# pic_circuit.net
KiCad netlist of a schematic drawn in EAGLE
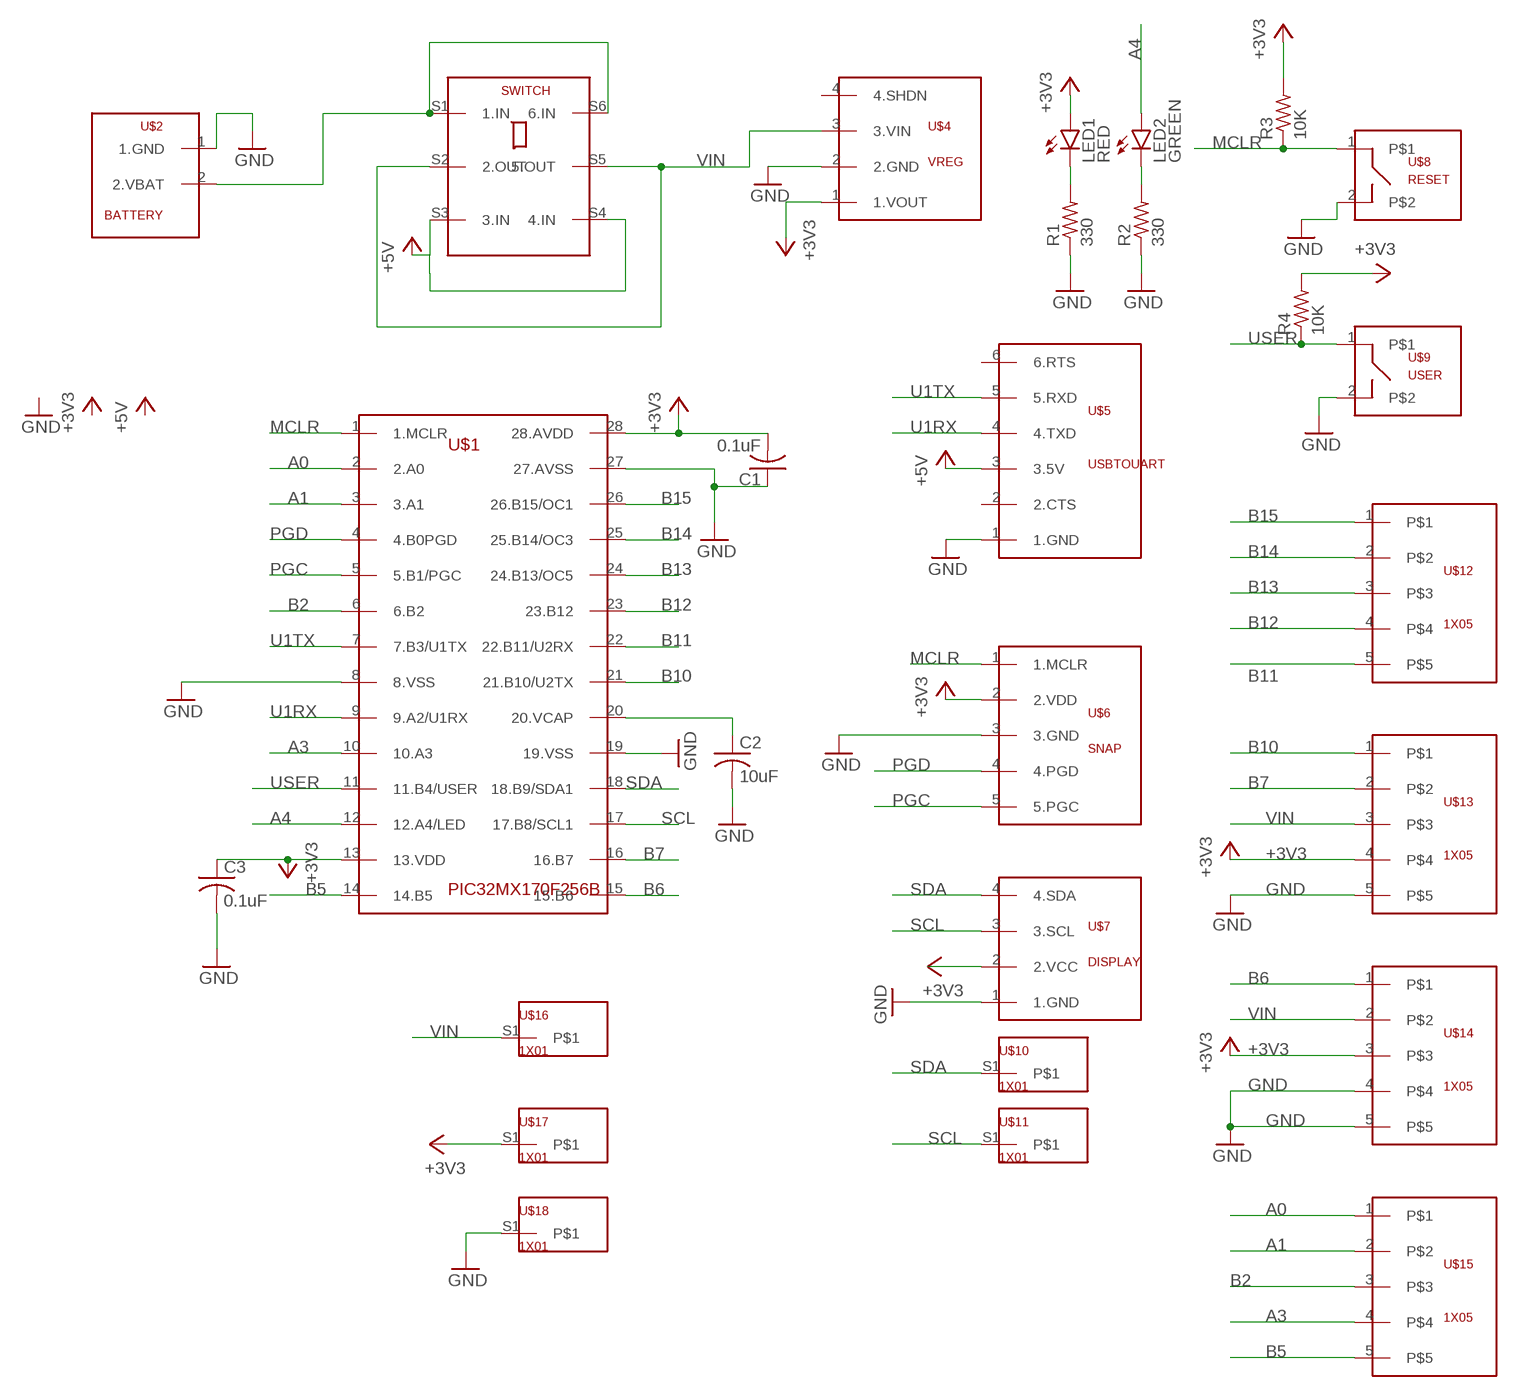
[diagram p0: schematic, sheet 1]

(export (version "E")
  (design (tool "Eeschema 10.0.6"))
  (components
    (comp (ref "C1")
      (value "0.1uF")
      (footprint "eagle-import:C025-024X044")
      (libsource (lib "eagle-import") (part "C-US025-024X044"))
    )
    (comp (ref "C2")
      (value "10uF")
      (footprint "eagle-import:C025-024X044")
      (libsource (lib "eagle-import") (part "C-US025-024X044"))
    )
    (comp (ref "C3")
      (value "0.1uF")
      (footprint "eagle-import:C025-024X044")
      (libsource (lib "eagle-import") (part "C-US025-024X044"))
    )
    (comp (ref "LED1")
      (value "RED")
      (footprint "eagle-import:LED3MM")
      (libsource (lib "eagle-import") (part "LED3MM"))
    )
    (comp (ref "LED2")
      (value "GREEN")
      (footprint "eagle-import:LED3MM")
      (libsource (lib "eagle-import") (part "LED3MM"))
    )
    (comp (ref "R1")
      (value "330")
      (footprint "eagle-import:0207_7")
      (libsource (lib "eagle-import") (part "R-US_0207/7"))
    )
    (comp (ref "R2")
      (value "330")
      (footprint "eagle-import:0207_7")
      (libsource (lib "eagle-import") (part "R-US_0207/7"))
    )
    (comp (ref "R3")
      (value "10K")
      (footprint "eagle-import:0207_7")
      (libsource (lib "eagle-import") (part "R-US_0207/7"))
    )
    (comp (ref "R4")
      (value "10K")
      (footprint "eagle-import:0207_7")
      (libsource (lib "eagle-import") (part "R-US_0207/7"))
    )
    (comp (ref "SWITCH")
      (value "SLIDE")
      (footprint "eagle-import:SWITCH")
      (libsource (lib "eagle-import") (part "SLIDE"))
    )
    (comp (ref "U$1")
      (value "PIC32MX170F256B")
      (footprint "eagle-import:DIL28-3")
      (libsource (lib "eagle-import") (part "PIC32MX170F256B"))
    )
    (comp (ref "U$2")
      (value "BATTERY")
      (footprint "eagle-import:BATTERY")
      (libsource (lib "eagle-import") (part "BATTERY"))
    )
    (comp (ref "U$4")
      (value "VREG")
      (footprint "eagle-import:VREG")
      (libsource (lib "eagle-import") (part "VREG"))
    )
    (comp (ref "U$5")
      (value "USBTOUART")
      (footprint "eagle-import:1X06")
      (libsource (lib "eagle-import") (part "USBTOUART"))
    )
    (comp (ref "U$6")
      (value "SNAP")
      (footprint "eagle-import:SNAP")
      (libsource (lib "eagle-import") (part "SNAP"))
    )
    (comp (ref "U$7")
      (value "DISPLAY")
      (footprint "eagle-import:DISPLAY")
      (libsource (lib "eagle-import") (part "DISPLAY"))
    )
    (comp (ref "U$8")
      (value "RESET")
      (footprint "eagle-import:BUTTON")
      (libsource (lib "eagle-import") (part "BUTTON"))
    )
    (comp (ref "U$9")
      (value "USER")
      (footprint "eagle-import:BUTTON")
      (libsource (lib "eagle-import") (part "BUTTON"))
    )
    (comp (ref "U$10")
      (value "1X01")
      (footprint "eagle-import:1X01_EE")
      (libsource (lib "eagle-import") (part "1X01"))
    )
    (comp (ref "U$11")
      (value "1X01")
      (footprint "eagle-import:1X01_EE")
      (libsource (lib "eagle-import") (part "1X01"))
    )
    (comp (ref "U$12")
      (value "1X05")
      (footprint "eagle-import:1X05_EE")
      (libsource (lib "eagle-import") (part "1X05"))
    )
    (comp (ref "U$13")
      (value "1X05")
      (footprint "eagle-import:1X05_EE")
      (libsource (lib "eagle-import") (part "1X05"))
    )
    (comp (ref "U$14")
      (value "1X05")
      (footprint "eagle-import:1X05_EE")
      (libsource (lib "eagle-import") (part "1X05"))
    )
    (comp (ref "U$15")
      (value "1X05")
      (footprint "eagle-import:1X05_EE")
      (libsource (lib "eagle-import") (part "1X05"))
    )
    (comp (ref "U$16")
      (value "1X01")
      (footprint "eagle-import:1X01_EE")
      (libsource (lib "eagle-import") (part "1X01"))
    )
    (comp (ref "U$17")
      (value "1X01")
      (footprint "eagle-import:1X01_EE")
      (libsource (lib "eagle-import") (part "1X01"))
    )
    (comp (ref "U$18")
      (value "1X01")
      (footprint "eagle-import:1X01_EE")
      (libsource (lib "eagle-import") (part "1X01"))
    )
  )
  (nets
    (net (code "1") (name "+3V3") (class "Default")
      (node (ref "C1") (pin "2") (pinfunction "2_2") (pintype "passive"))
      (node (ref "C3") (pin "1") (pinfunction "1_1") (pintype "passive"))
      (node (ref "LED1") (pin "A") (pinfunction "A_A") (pintype "passive"))
      (node (ref "R3") (pin "2") (pinfunction "2_2") (pintype "passive"))
      (node (ref "R4") (pin "2") (pinfunction "2_2") (pintype "passive"))
      (node (ref "U$1") (pin "13") (pinfunction "13.VDD_13") (pintype "bidirectional"))
      (node (ref "U$1") (pin "28") (pinfunction "28.AVDD_28") (pintype "bidirectional"))
      (node (ref "U$13") (pin "4") (pinfunction "P$4_4") (pintype "bidirectional"))
      (node (ref "U$14") (pin "3") (pinfunction "P$3_3") (pintype "bidirectional"))
      (node (ref "U$17") (pin "S1") (pinfunction "P$1_S1") (pintype "bidirectional"))
      (node (ref "U$4") (pin "1") (pinfunction "1.VOUT_1") (pintype "bidirectional"))
      (node (ref "U$6") (pin "2") (pinfunction "2.VDD_2") (pintype "bidirectional"))
      (node (ref "U$7") (pin "2") (pinfunction "2.VCC_2") (pintype "bidirectional"))
    )
    (net (code "2") (name "+5V") (class "Default")
      (node (ref "SWITCH") (pin "S3") (pinfunction "3.IN_S3") (pintype "bidirectional"))
      (node (ref "SWITCH") (pin "S4") (pinfunction "4.IN_S4") (pintype "bidirectional"))
      (node (ref "U$5") (pin "3") (pinfunction "3.5V_3") (pintype "bidirectional"))
    )
    (net (code "3") (name "/A0") (class "Default")
      (node (ref "U$1") (pin "2") (pinfunction "2.A0_2") (pintype "bidirectional"))
      (node (ref "U$15") (pin "1") (pinfunction "P$1_1") (pintype "bidirectional"))
    )
    (net (code "4") (name "/A1") (class "Default")
      (node (ref "U$1") (pin "3") (pinfunction "3.A1_3") (pintype "bidirectional"))
      (node (ref "U$15") (pin "2") (pinfunction "P$2_2") (pintype "bidirectional"))
    )
    (net (code "5") (name "/A3") (class "Default")
      (node (ref "U$1") (pin "10") (pinfunction "10.A3_10") (pintype "bidirectional"))
      (node (ref "U$15") (pin "4") (pinfunction "P$4_4") (pintype "bidirectional"))
    )
    (net (code "6") (name "/A4") (class "Default")
      (node (ref "LED2") (pin "A") (pinfunction "A_A") (pintype "passive"))
      (node (ref "U$1") (pin "12") (pinfunction "12.A4/LED_12") (pintype "bidirectional"))
    )
    (net (code "7") (name "/B2") (class "Default")
      (node (ref "U$1") (pin "6") (pinfunction "6.B2_6") (pintype "bidirectional"))
      (node (ref "U$15") (pin "3") (pinfunction "P$3_3") (pintype "bidirectional"))
    )
    (net (code "8") (name "/B5") (class "Default")
      (node (ref "U$1") (pin "14") (pinfunction "14.B5_14") (pintype "bidirectional"))
      (node (ref "U$15") (pin "5") (pinfunction "P$5_5") (pintype "bidirectional"))
    )
    (net (code "9") (name "/B6") (class "Default")
      (node (ref "U$1") (pin "15") (pinfunction "15.B6_15") (pintype "bidirectional"))
      (node (ref "U$14") (pin "1") (pinfunction "P$1_1") (pintype "bidirectional"))
    )
    (net (code "10") (name "/B7") (class "Default")
      (node (ref "U$1") (pin "16") (pinfunction "16.B7_16") (pintype "bidirectional"))
      (node (ref "U$13") (pin "2") (pinfunction "P$2_2") (pintype "bidirectional"))
    )
    (net (code "11") (name "/B10") (class "Default")
      (node (ref "U$1") (pin "21") (pinfunction "21.B10/U2TX_21") (pintype "bidirectional"))
      (node (ref "U$13") (pin "1") (pinfunction "P$1_1") (pintype "bidirectional"))
    )
    (net (code "12") (name "/B11") (class "Default")
      (node (ref "U$1") (pin "22") (pinfunction "22.B11/U2RX_22") (pintype "bidirectional"))
      (node (ref "U$12") (pin "5") (pinfunction "P$5_5") (pintype "bidirectional"))
    )
    (net (code "13") (name "/B12") (class "Default")
      (node (ref "U$1") (pin "23") (pinfunction "23.B12_23") (pintype "bidirectional"))
      (node (ref "U$12") (pin "4") (pinfunction "P$4_4") (pintype "bidirectional"))
    )
    (net (code "14") (name "/B13") (class "Default")
      (node (ref "U$1") (pin "24") (pinfunction "24.B13/OC5_24") (pintype "bidirectional"))
      (node (ref "U$12") (pin "3") (pinfunction "P$3_3") (pintype "bidirectional"))
    )
    (net (code "15") (name "/B14") (class "Default")
      (node (ref "U$1") (pin "25") (pinfunction "25.B14/OC3_25") (pintype "bidirectional"))
      (node (ref "U$12") (pin "2") (pinfunction "P$2_2") (pintype "bidirectional"))
    )
    (net (code "16") (name "/B15") (class "Default")
      (node (ref "U$1") (pin "26") (pinfunction "26.B15/OC1_26") (pintype "bidirectional"))
      (node (ref "U$12") (pin "1") (pinfunction "P$1_1") (pintype "bidirectional"))
    )
    (net (code "17") (name "/MCLR") (class "Default")
      (node (ref "R3") (pin "1") (pinfunction "1_1") (pintype "passive"))
      (node (ref "U$1") (pin "1") (pinfunction "1.MCLR_1") (pintype "bidirectional"))
      (node (ref "U$6") (pin "1") (pinfunction "1.MCLR_1") (pintype "bidirectional"))
      (node (ref "U$8") (pin "1") (pinfunction "P$1_1") (pintype "bidirectional"))
    )
    (net (code "18") (name "/PGC") (class "Default")
      (node (ref "U$1") (pin "5") (pinfunction "5.B1/PGC_5") (pintype "bidirectional"))
      (node (ref "U$6") (pin "5") (pinfunction "5.PGC_5") (pintype "bidirectional"))
    )
    (net (code "19") (name "/PGD") (class "Default")
      (node (ref "U$1") (pin "4") (pinfunction "4.B0PGD_4") (pintype "bidirectional"))
      (node (ref "U$6") (pin "4") (pinfunction "4.PGD_4") (pintype "bidirectional"))
    )
    (net (code "20") (name "/SCL") (class "Default")
      (node (ref "U$1") (pin "17") (pinfunction "17.B8/SCL1_17") (pintype "bidirectional"))
      (node (ref "U$11") (pin "S1") (pinfunction "P$1_S1") (pintype "bidirectional"))
      (node (ref "U$7") (pin "3") (pinfunction "3.SCL_3") (pintype "bidirectional"))
    )
    (net (code "21") (name "/SDA") (class "Default")
      (node (ref "U$1") (pin "18") (pinfunction "18.B9/SDA1_18") (pintype "bidirectional"))
      (node (ref "U$10") (pin "S1") (pinfunction "P$1_S1") (pintype "bidirectional"))
      (node (ref "U$7") (pin "4") (pinfunction "4.SDA_4") (pintype "bidirectional"))
    )
    (net (code "22") (name "/U1RX") (class "Default")
      (node (ref "U$1") (pin "9") (pinfunction "9.A2/U1RX_9") (pintype "bidirectional"))
      (node (ref "U$5") (pin "4") (pinfunction "4.TXD_4") (pintype "bidirectional"))
    )
    (net (code "23") (name "/U1TX") (class "Default")
      (node (ref "U$1") (pin "7") (pinfunction "7.B3/U1TX_7") (pintype "bidirectional"))
      (node (ref "U$5") (pin "5") (pinfunction "5.RXD_5") (pintype "bidirectional"))
    )
    (net (code "24") (name "/USER") (class "Default")
      (node (ref "R4") (pin "1") (pinfunction "1_1") (pintype "passive"))
      (node (ref "U$1") (pin "11") (pinfunction "11.B4/USER_11") (pintype "bidirectional"))
      (node (ref "U$9") (pin "1") (pinfunction "P$1_1") (pintype "bidirectional"))
    )
    (net (code "25") (name "/VIN") (class "Default")
      (node (ref "SWITCH") (pin "S2") (pinfunction "2.OUT_S2") (pintype "bidirectional"))
      (node (ref "SWITCH") (pin "S5") (pinfunction "5.OUT_S5") (pintype "bidirectional"))
      (node (ref "U$13") (pin "3") (pinfunction "P$3_3") (pintype "bidirectional"))
      (node (ref "U$14") (pin "2") (pinfunction "P$2_2") (pintype "bidirectional"))
      (node (ref "U$16") (pin "S1") (pinfunction "P$1_S1") (pintype "bidirectional"))
      (node (ref "U$4") (pin "3") (pinfunction "3.VIN_3") (pintype "bidirectional"))
    )
    (net (code "26") (name "GND") (class "Default")
      (node (ref "C1") (pin "1") (pinfunction "1_1") (pintype "passive"))
      (node (ref "C2") (pin "2") (pinfunction "2_2") (pintype "passive"))
      (node (ref "C3") (pin "2") (pinfunction "2_2") (pintype "passive"))
      (node (ref "R1") (pin "1") (pinfunction "1_1") (pintype "passive"))
      (node (ref "R2") (pin "1") (pinfunction "1_1") (pintype "passive"))
      (node (ref "U$1") (pin "19") (pinfunction "19.VSS_19") (pintype "bidirectional"))
      (node (ref "U$1") (pin "27") (pinfunction "27.AVSS_27") (pintype "bidirectional"))
      (node (ref "U$1") (pin "8") (pinfunction "8.VSS_8") (pintype "bidirectional"))
      (node (ref "U$13") (pin "5") (pinfunction "P$5_5") (pintype "bidirectional"))
      (node (ref "U$14") (pin "4") (pinfunction "P$4_4") (pintype "bidirectional"))
      (node (ref "U$14") (pin "5") (pinfunction "P$5_5") (pintype "bidirectional"))
      (node (ref "U$18") (pin "S1") (pinfunction "P$1_S1") (pintype "bidirectional"))
      (node (ref "U$2") (pin "1") (pinfunction "1.GND_1") (pintype "bidirectional"))
      (node (ref "U$4") (pin "2") (pinfunction "2.GND_2") (pintype "bidirectional"))
      (node (ref "U$5") (pin "1") (pinfunction "1.GND_1") (pintype "bidirectional"))
      (node (ref "U$6") (pin "3") (pinfunction "3.GND_3") (pintype "bidirectional"))
      (node (ref "U$7") (pin "1") (pinfunction "1.GND_1") (pintype "bidirectional"))
      (node (ref "U$8") (pin "2") (pinfunction "P$2_2") (pintype "bidirectional"))
      (node (ref "U$9") (pin "2") (pinfunction "P$2_2") (pintype "bidirectional"))
    )
    (net (code "27") (name "Net-(LED1-C)") (class "Default")
      (node (ref "LED1") (pin "K") (pinfunction "C_K") (pintype "passive"))
      (node (ref "R1") (pin "2") (pinfunction "2_2") (pintype "passive"))
    )
    (net (code "28") (name "Net-(LED2-C)") (class "Default")
      (node (ref "LED2") (pin "K") (pinfunction "C_K") (pintype "passive"))
      (node (ref "R2") (pin "2") (pinfunction "2_2") (pintype "passive"))
    )
    (net (code "29") (name "Net-(SWITCH-1.IN)") (class "Default")
      (node (ref "SWITCH") (pin "S1") (pinfunction "1.IN_S1") (pintype "bidirectional"))
      (node (ref "SWITCH") (pin "S6") (pinfunction "6.IN_S6") (pintype "bidirectional"))
      (node (ref "U$2") (pin "2") (pinfunction "2.VBAT_2") (pintype "bidirectional"))
    )
    (net (code "30") (name "Net-(U$1-20.VCAP)") (class "Default")
      (node (ref "C2") (pin "1") (pinfunction "1_1") (pintype "passive"))
      (node (ref "U$1") (pin "20") (pinfunction "20.VCAP_20") (pintype "bidirectional"))
    )
    (net (code "31") (name "unconnected-(U$4-4.SHDN-Pad4)") (class "Default")
      (node (ref "U$4") (pin "4") (pinfunction "4.SHDN_4") (pintype "bidirectional"))
    )
    (net (code "32") (name "unconnected-(U$5-2.CTS-Pad2)") (class "Default")
      (node (ref "U$5") (pin "2") (pinfunction "2.CTS_2") (pintype "bidirectional"))
    )
    (net (code "33") (name "unconnected-(U$5-6.RTS-Pad6)") (class "Default")
      (node (ref "U$5") (pin "6") (pinfunction "6.RTS_6") (pintype "bidirectional"))
    )
  )
)
